# H01R0_Backend.net
KiCad netlist of a schematic drawn in Altium Designer
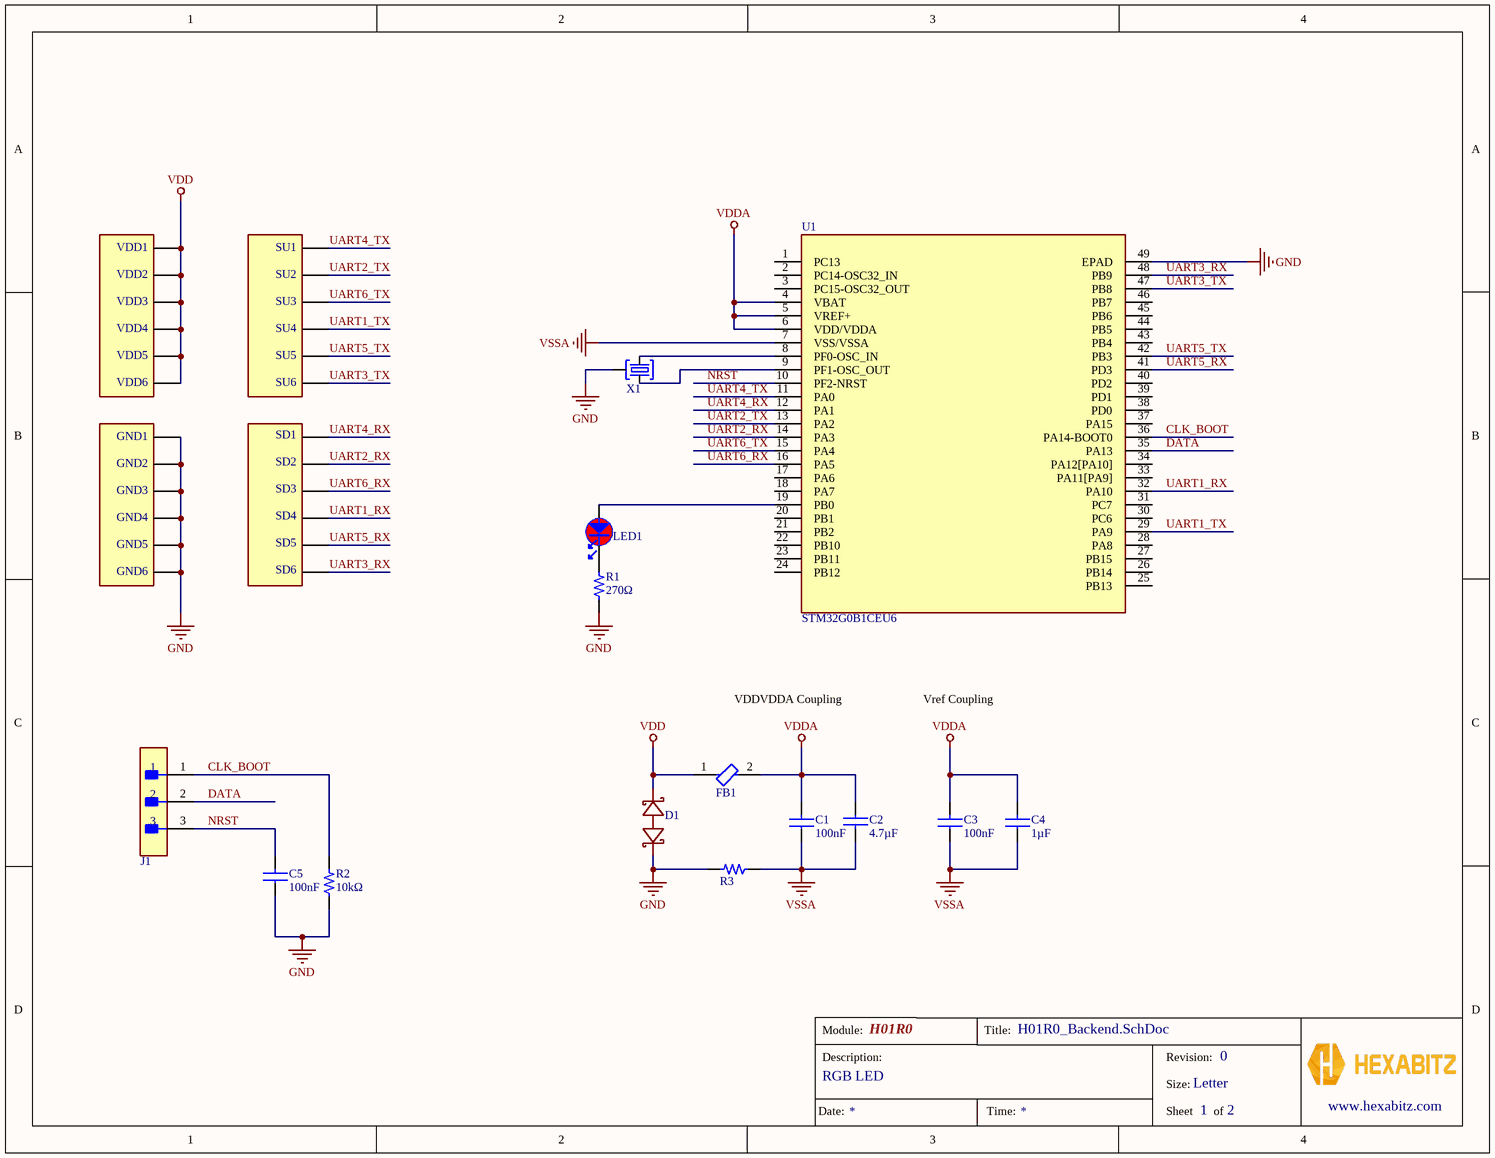
[diagram p0: H01R0_Backend.SchDoc]

(export (version "E")
  (design (tool "Eeschema 10.0.6"))
  (components
    (comp (ref "C1")
      (value "100nF")
      (footprint "C0603")
      (fields
        (field (name "MANUFACTURER") "Samsung Electro-Mechanics")
        (field (name "MANUFACTURER PART NUMBER") "CL10B104KA8NNNC")
        (field (name "TOLERANCE") "10%")
      )
      (libsource (lib "Hexabitz Altium Library") (part "generic Capacitor"))
    )
    (comp (ref "C2")
      (value "4.7µF")
      (footprint "C0805")
      (fields
        (field (name "MANUFACTURER") "Samsung Electro-Mechanics")
        (field (name "MANUFACTURER PART NUMBER") "CL21X475KAQNNNE")
        (field (name "TOLERANCE") "10%")
      )
      (libsource (lib "Hexabitz Altium Library") (part "generic Capacitor"))
    )
    (comp (ref "C3")
      (value "100nF")
      (footprint "C0603")
      (fields
        (field (name "MANUFACTURER") "Samsung Electro-Mechanics")
        (field (name "MANUFACTURER PART NUMBER") "CL10B104KA8NNNC")
        (field (name "TOLERANCE") "10%")
      )
      (libsource (lib "Hexabitz Altium Library") (part "generic Capacitor"))
    )
    (comp (ref "C4")
      (value "1µF")
      (footprint "C0805")
      (description "Ceramic Capacitor, Ceramic, 16V, 10% +Tol, 10% -Tol, X7R, 15% TC, 1uF, Surface Mount, 0805")
      (fields
        (field (name "MANUFACTURER") "Yageo Group")
        (field (name "MANUFACTURER PART NUMBER") "CC0805KKX7R7BB105")
      )
      (libsource (lib "Hexabitz Altium Library") (part "generic Capacitor"))
    )
    (comp (ref "C5")
      (value "100nF")
      (footprint "C0603")
      (fields
        (field (name "MANUFACTURER") "Samsung Electro-Mechanics")
        (field (name "MANUFACTURER PART NUMBER") "CL10B104KA8NNNC")
        (field (name "TOLERANCE") "10%")
      )
      (libsource (lib "Hexabitz Altium Library") (part "generic Capacitor"))
    )
    (comp (ref "D1")
      (value "CDSOD323-T03SC")
      (footprint "SOD2513X114N")
      (description "A 3V, 350W, bi-directional, standard capacitance, SOD323 pkg TVS Diode ¦ Bourns CDSOD323-T03SC")
      (fields (field (name "MANUFACTURER") "Bourns"))
      (libsource (lib "Hexabitz Altium Library") (part "CDSOD323-T03SC"))
    )
    (comp (ref "FB1")
      (value "MMZ1608Y300B")
      (footprint "FP-MMZ1608-0_8-MFG")
      (description "Ferrite Beads 0603 30ohms 1500mA Signal Line AEC-Q200")
      (fields
        (field (name "MANUFACTURER") "TDK")
        (field (name "MANUFACTURER PART NUMBER") "MMZ1608Y300BTD25")
      )
      (libsource (lib "Hexabitz Altium Library") (part "MMZ1608Y300B"))
    )
    (comp (ref "GND1")
      (value "HEXABIT_UART_PORT")
      (footprint "HEXABIT_POWER_PORT_D")
      (libsource (lib "hexabitz_connectors.Library") (part "HEXABIT_POWER_PORT_D"))
    )
    (comp (ref "GND2")
      (value "HEXABIT_UART_PORT")
      (footprint "HEXABIT_POWER_PORT_D")
      (libsource (lib "hexabitz_connectors.Library") (part "HEXABIT_POWER_PORT_D"))
    )
    (comp (ref "GND3")
      (value "HEXABIT_UART_PORT")
      (footprint "HEXABIT_POWER_PORT_D")
      (libsource (lib "hexabitz_connectors.Library") (part "HEXABIT_POWER_PORT_D"))
    )
    (comp (ref "GND4")
      (value "HEXABIT_UART_PORT")
      (footprint "HEXABIT_POWER_PORT_D")
      (libsource (lib "hexabitz_connectors.Library") (part "HEXABIT_POWER_PORT_D"))
    )
    (comp (ref "GND5")
      (value "HEXABIT_UART_PORT")
      (footprint "HEXABIT_POWER_PORT_D")
      (libsource (lib "hexabitz_connectors.Library") (part "HEXABIT_POWER_PORT_D"))
    )
    (comp (ref "GND6")
      (value "HEXABIT_UART_PORT")
      (footprint "HEXABIT_POWER_PORT_D")
      (libsource (lib "hexabitz_connectors.Library") (part "HEXABIT_POWER_PORT_D"))
    )
    (comp (ref "J1")
      (value "TSW-103-14-G-S")
      (footprint "FP-TSW-103-14-G-S-MFG")
      (description "CONN HEADER VERT 3POS 2.54MM")
      (libsource (lib "Altium Content Vault") (part "cd3439d6ef35ae5d9b27ec4fdd3e828"))
    )
    (comp (ref "LED1")
      (value "VLMS1300-GS08")
      (footprint "FP-6_541-5092_01-4-MFG")
      (description "LED Uni-Color Super Red 639nm 2-Pin Chip 0603(1608Metric) T/R")
      (fields (field (name "MANUFACTURER") "Vishay Semiconductors"))
      (libsource (lib "Hexabitz Altium Library") (part "VLMS1300-GS08"))
    )
    (comp (ref "R1")
      (value "270Ω")
      (footprint "R0603")
      (description "Res Thick Film 0603 270 Ohm 5% 0.1W(1/10W) ±200ppm/C Pad SMD Automotive T/R")
      (fields
        (field (name "MANUFACTURER") "Panasonic")
        (field (name "MANUFACTURER PART NUMBER") "ERJ-3GEYJ271V")
      )
      (libsource (lib "Hexabitz Altium Library") (part "generic Resistor"))
    )
    (comp (ref "R2")
      (value "10kΩ")
      (footprint "R0603")
      (description "100mW Thick Film Resistors ±100ppm/℃ ±1% 10kΩ 0603 Chip Resistor - Surface Mount ROHS")
      (fields
        (field (name "MANUFACTURER") "Yageo Group")
        (field (name "MANUFACTURER PART NUMBER") "RC0603FR-0710KL")
      )
      (libsource (lib "") (part "generic Resistor_1"))
    )
    (comp (ref "R3")
      (value "Manufacturer Part Number")
      (footprint "R0603")
      (libsource (lib "") (part "generic Resistor_2"))
    )
    (comp (ref "SD1")
      (value "HEXABIT_UART_PORT")
      (footprint "HEXABIT_UART_PORT_D")
      (libsource (lib "hexabitz_connectors.Library") (part "HEXABIT_UART_PORT_D"))
    )
    (comp (ref "SD2")
      (value "HEXABIT_UART_PORT")
      (footprint "HEXABIT_UART_PORT_D")
      (libsource (lib "hexabitz_connectors.Library") (part "HEXABIT_UART_PORT_D"))
    )
    (comp (ref "SD3")
      (value "HEXABIT_UART_PORT")
      (footprint "HEXABIT_UART_PORT_D")
      (libsource (lib "hexabitz_connectors.Library") (part "HEXABIT_UART_PORT_D"))
    )
    (comp (ref "SD4")
      (value "HEXABIT_UART_PORT")
      (footprint "HEXABIT_UART_PORT_D")
      (libsource (lib "hexabitz_connectors.Library") (part "HEXABIT_UART_PORT_D"))
    )
    (comp (ref "SD5")
      (value "HEXABIT_UART_PORT")
      (footprint "HEXABIT_UART_PORT_D")
      (libsource (lib "hexabitz_connectors.Library") (part "HEXABIT_UART_PORT_D"))
    )
    (comp (ref "SD6")
      (value "HEXABIT_UART_PORT")
      (footprint "HEXABIT_UART_PORT_D")
      (libsource (lib "hexabitz_connectors.Library") (part "HEXABIT_UART_PORT_D"))
    )
    (comp (ref "SU1")
      (value "HEXABIT_UART_PORT")
      (footprint "HEXABIT_UART_PORT_U")
      (libsource (lib "hexabitz_connectors.Library") (part "HEXABIT_UART_PORT_U"))
    )
    (comp (ref "SU2")
      (value "HEXABIT_UART_PORT")
      (footprint "HEXABIT_UART_PORT_U")
      (libsource (lib "hexabitz_connectors.Library") (part "HEXABIT_UART_PORT_U"))
    )
    (comp (ref "SU3")
      (value "HEXABIT_UART_PORT")
      (footprint "HEXABIT_UART_PORT_U")
      (libsource (lib "hexabitz_connectors.Library") (part "HEXABIT_UART_PORT_U"))
    )
    (comp (ref "SU4")
      (value "HEXABIT_UART_PORT")
      (footprint "HEXABIT_UART_PORT_U")
      (libsource (lib "hexabitz_connectors.Library") (part "HEXABIT_UART_PORT_U"))
    )
    (comp (ref "SU5")
      (value "HEXABIT_UART_PORT")
      (footprint "HEXABIT_UART_PORT_U")
      (libsource (lib "hexabitz_connectors.Library") (part "HEXABIT_UART_PORT_U"))
    )
    (comp (ref "SU6")
      (value "HEXABIT_UART_PORT")
      (footprint "HEXABIT_UART_PORT_U")
      (libsource (lib "hexabitz_connectors.Library") (part "HEXABIT_UART_PORT_U"))
    )
    (comp (ref "U1")
      (value "STM32G0B1CEU6")
      (footprint "QFN50P700X700X65-49N-D")
      (description "MCU 32-bit ARM Cortex M0+ RISC 512KB Flash 1.8V/2.5V/3.3V 48-Pin UFQFPN EP Tray")
      (fields
        (field (name "MANUFACTURER") "STMicroelectronics")
        (field (name "MANUFACTURER PART NUMBER") "STM32G0B1CEU6")
      )
      (libsource (lib "Hexabitz Altium Library") (part "STM32G0B1CEU6"))
    )
    (comp (ref "VDD1")
      (value "HEXABIT_UART_PORT")
      (footprint "HEXABIT_POWER_PORT_U")
      (libsource (lib "hexabitz_connectors.Library") (part "HEXABIT_POWER_PORT_U"))
    )
    (comp (ref "VDD2")
      (value "HEXABIT_UART_PORT")
      (footprint "HEXABIT_POWER_PORT_U")
      (libsource (lib "hexabitz_connectors.Library") (part "HEXABIT_POWER_PORT_U"))
    )
    (comp (ref "VDD3")
      (value "HEXABIT_UART_PORT")
      (footprint "HEXABIT_POWER_PORT_U")
      (libsource (lib "hexabitz_connectors.Library") (part "HEXABIT_POWER_PORT_U"))
    )
    (comp (ref "VDD4")
      (value "HEXABIT_UART_PORT")
      (footprint "HEXABIT_POWER_PORT_U")
      (libsource (lib "hexabitz_connectors.Library") (part "HEXABIT_POWER_PORT_U"))
    )
    (comp (ref "VDD5")
      (value "HEXABIT_UART_PORT")
      (footprint "HEXABIT_POWER_PORT_U")
      (libsource (lib "hexabitz_connectors.Library") (part "HEXABIT_POWER_PORT_U"))
    )
    (comp (ref "VDD6")
      (value "HEXABIT_UART_PORT")
      (footprint "HEXABIT_POWER_PORT_U")
      (libsource (lib "hexabitz_connectors.Library") (part "HEXABIT_POWER_PORT_U"))
    )
    (comp (ref "X1")
      (value "CSTCE8M00G52Z-R0")
      (footprint "XTALL_CSTCE8M00G52")
      (description "Ceramic Resonator 8MHz ±0.5% (Tol) ±0.2% (Stability) 10pF 40Ohm 3-Pin CSMD T/R")
      (fields (field (name "MANUFACTURER") "Murata") (field (name "TOLERANCE") "0.5%"))
      (libsource (lib "Hexabitz Altium Library") (part "CSTCE8M00G52Z-R0"))
    )
  )
  (nets
    (net (code "1") (name "/CLK_BOOT") (class "Default")
      (node (ref "J1") (pin "1") (pinfunction "1_1") (pintype "passive"))
      (node (ref "R2") (pin "1") (pinfunction "1_1") (pintype "passive"))
      (node (ref "U1") (pin "36") (pinfunction "PA14-BOOT0_36") (pintype "passive"))
    )
    (net (code "2") (name "/DATA") (class "Default")
      (node (ref "J1") (pin "2") (pinfunction "2_2") (pintype "passive"))
      (node (ref "U1") (pin "35") (pinfunction "PA13_35") (pintype "passive"))
    )
    (net (code "3") (name "/NRST") (class "Default")
      (node (ref "C5") (pin "2") (pinfunction "2_2") (pintype "passive"))
      (node (ref "J1") (pin "3") (pinfunction "3_3") (pintype "passive"))
      (node (ref "U1") (pin "10") (pinfunction "PF2-NRST_10") (pintype "passive"))
    )
    (net (code "4") (name "/UART1_RX") (class "Default")
      (node (ref "SD4") (pin "UART_D") (pinfunction "UART_D_UART_D") (pintype "passive"))
      (node (ref "U1") (pin "32") (pinfunction "PA10_32") (pintype "passive"))
    )
    (net (code "5") (name "/UART1_TX") (class "Default")
      (node (ref "SU4") (pin "UART_U") (pinfunction "UART_U_UART_U") (pintype "passive"))
      (node (ref "U1") (pin "29") (pinfunction "PA9_29") (pintype "passive"))
    )
    (net (code "6") (name "/UART2_RX") (class "Default")
      (node (ref "SD2") (pin "UART_D") (pinfunction "UART_D_UART_D") (pintype "passive"))
      (node (ref "U1") (pin "14") (pinfunction "PA3_14") (pintype "passive"))
    )
    (net (code "7") (name "/UART2_TX") (class "Default")
      (node (ref "SU2") (pin "UART_U") (pinfunction "UART_U_UART_U") (pintype "passive"))
      (node (ref "U1") (pin "13") (pinfunction "PA2_13") (pintype "passive"))
    )
    (net (code "8") (name "/UART3_RX") (class "Default")
      (node (ref "SD6") (pin "UART_D") (pinfunction "UART_D_UART_D") (pintype "passive"))
      (node (ref "U1") (pin "48") (pinfunction "PB9_48") (pintype "passive"))
    )
    (net (code "9") (name "/UART3_TX") (class "Default")
      (node (ref "SU6") (pin "UART_U") (pinfunction "UART_U_UART_U") (pintype "passive"))
      (node (ref "U1") (pin "47") (pinfunction "PB8_47") (pintype "passive"))
    )
    (net (code "10") (name "/UART4_RX") (class "Default")
      (node (ref "SD1") (pin "UART_D") (pinfunction "UART_D_UART_D") (pintype "passive"))
      (node (ref "U1") (pin "12") (pinfunction "PA1_12") (pintype "passive"))
    )
    (net (code "11") (name "/UART4_TX") (class "Default")
      (node (ref "SU1") (pin "UART_U") (pinfunction "UART_U_UART_U") (pintype "passive"))
      (node (ref "U1") (pin "11") (pinfunction "PA0_11") (pintype "passive"))
    )
    (net (code "12") (name "/UART5_RX") (class "Default")
      (node (ref "SD5") (pin "UART_D") (pinfunction "UART_D_UART_D") (pintype "passive"))
      (node (ref "U1") (pin "41") (pinfunction "PD3_41") (pintype "passive"))
    )
    (net (code "13") (name "/UART5_TX") (class "Default")
      (node (ref "SU5") (pin "UART_U") (pinfunction "UART_U_UART_U") (pintype "passive"))
      (node (ref "U1") (pin "42") (pinfunction "PB3_42") (pintype "passive"))
    )
    (net (code "14") (name "/UART6_RX") (class "Default")
      (node (ref "SD3") (pin "UART_D") (pinfunction "UART_D_UART_D") (pintype "passive"))
      (node (ref "U1") (pin "16") (pinfunction "PA5_16") (pintype "passive"))
    )
    (net (code "15") (name "/UART6_TX") (class "Default")
      (node (ref "SU3") (pin "UART_U") (pinfunction "UART_U_UART_U") (pintype "passive"))
      (node (ref "U1") (pin "15") (pinfunction "PA4_15") (pintype "passive"))
    )
    (net (code "16") (name "GND") (class "Default")
      (node (ref "C5") (pin "1") (pinfunction "1_1") (pintype "passive"))
      (node (ref "D1") (pin "1") (pinfunction "A_1") (pintype "passive"))
      (node (ref "GND1") (pin "Pwr_D") (pinfunction "Pwr_D_Pwr_D") (pintype "passive"))
      (node (ref "GND2") (pin "Pwr_D") (pinfunction "Pwr_D_Pwr_D") (pintype "passive"))
      (node (ref "GND3") (pin "Pwr_D") (pinfunction "Pwr_D_Pwr_D") (pintype "passive"))
      (node (ref "GND4") (pin "Pwr_D") (pinfunction "Pwr_D_Pwr_D") (pintype "passive"))
      (node (ref "GND5") (pin "Pwr_D") (pinfunction "Pwr_D_Pwr_D") (pintype "passive"))
      (node (ref "GND6") (pin "Pwr_D") (pinfunction "Pwr_D_Pwr_D") (pintype "passive"))
      (node (ref "R1") (pin "1") (pinfunction "1_1") (pintype "passive"))
      (node (ref "R2") (pin "2") (pinfunction "2_2") (pintype "passive"))
      (node (ref "R3") (pin "1") (pinfunction "1_1") (pintype "passive"))
      (node (ref "U1") (pin "49") (pinfunction "EPAD_49") (pintype "passive"))
      (node (ref "X1") (pin "P$2") (pinfunction "2_P$2") (pintype "passive"))
    )
    (net (code "17") (name "Net-(LED1-Pad1)") (class "Default")
      (node (ref "LED1") (pin "1") (pintype "passive"))
      (node (ref "R1") (pin "2") (pinfunction "2_2") (pintype "passive"))
    )
    (net (code "18") (name "Net-(U1-PB0)") (class "Default")
      (node (ref "LED1") (pin "2") (pintype "passive"))
      (node (ref "U1") (pin "19") (pinfunction "PB0_19") (pintype "passive"))
    )
    (net (code "19") (name "Net-(U1-PF0-OSC_IN)") (class "Default")
      (node (ref "U1") (pin "8") (pinfunction "PF0-OSC_IN_8") (pintype "passive"))
      (node (ref "X1") (pin "P$3") (pinfunction "3_P$3") (pintype "passive"))
    )
    (net (code "20") (name "Net-(U1-PF1-OSC_OUT)") (class "Default")
      (node (ref "U1") (pin "9") (pinfunction "PF1-OSC_OUT_9") (pintype "passive"))
      (node (ref "X1") (pin "P$1") (pinfunction "1_P$1") (pintype "passive"))
    )
    (net (code "21") (name "VDD") (class "Default")
      (node (ref "D1") (pin "2") (pinfunction "C_2") (pintype "passive"))
      (node (ref "FB1") (pin "1") (pinfunction "1_1") (pintype "passive"))
      (node (ref "VDD1") (pin "Pwr_U") (pinfunction "Pwr_U_Pwr_U") (pintype "passive"))
      (node (ref "VDD2") (pin "Pwr_U") (pinfunction "Pwr_U_Pwr_U") (pintype "passive"))
      (node (ref "VDD3") (pin "Pwr_U") (pinfunction "Pwr_U_Pwr_U") (pintype "passive"))
      (node (ref "VDD4") (pin "Pwr_U") (pinfunction "Pwr_U_Pwr_U") (pintype "passive"))
      (node (ref "VDD5") (pin "Pwr_U") (pinfunction "Pwr_U_Pwr_U") (pintype "passive"))
      (node (ref "VDD6") (pin "Pwr_U") (pinfunction "Pwr_U_Pwr_U") (pintype "passive"))
    )
    (net (code "22") (name "VDDA") (class "Default")
      (node (ref "C1") (pin "2") (pinfunction "2_2") (pintype "passive"))
      (node (ref "C2") (pin "1") (pinfunction "1_1") (pintype "passive"))
      (node (ref "C3") (pin "2") (pinfunction "2_2") (pintype "passive"))
      (node (ref "C4") (pin "2") (pinfunction "2_2") (pintype "passive"))
      (node (ref "FB1") (pin "2") (pinfunction "2_2") (pintype "passive"))
      (node (ref "U1") (pin "4") (pinfunction "VBAT_4") (pintype "passive"))
      (node (ref "U1") (pin "5") (pinfunction "VREF+_5") (pintype "passive"))
      (node (ref "U1") (pin "6") (pinfunction "VDD/VDDA_6") (pintype "passive"))
    )
    (net (code "23") (name "VSSA") (class "Default")
      (node (ref "C1") (pin "1") (pinfunction "1_1") (pintype "passive"))
      (node (ref "C2") (pin "2") (pinfunction "2_2") (pintype "passive"))
      (node (ref "C3") (pin "1") (pinfunction "1_1") (pintype "passive"))
      (node (ref "C4") (pin "1") (pinfunction "1_1") (pintype "passive"))
      (node (ref "R3") (pin "2") (pinfunction "2_2") (pintype "passive"))
      (node (ref "U1") (pin "7") (pinfunction "VSS/VSSA_7") (pintype "passive"))
    )
    (net (code "24") (name "unconnected-(U1-PA6-Pad17)") (class "Default")
      (node (ref "U1") (pin "17") (pinfunction "PA6_17") (pintype "passive"))
    )
    (net (code "25") (name "unconnected-(U1-PA7-Pad18)") (class "Default")
      (node (ref "U1") (pin "18") (pinfunction "PA7_18") (pintype "passive"))
    )
    (net (code "26") (name "unconnected-(U1-PA8-Pad28)") (class "Default")
      (node (ref "U1") (pin "28") (pinfunction "PA8_28") (pintype "passive"))
    )
    (net (code "27") (name "unconnected-(U1-PA11[PA9]-Pad33)") (class "Default")
      (node (ref "U1") (pin "33") (pinfunction "PA11[PA9]_33") (pintype "passive"))
    )
    (net (code "28") (name "unconnected-(U1-PA12[PA10]-Pad34)") (class "Default")
      (node (ref "U1") (pin "34") (pinfunction "PA12[PA10]_34") (pintype "passive"))
    )
    (net (code "29") (name "unconnected-(U1-PA15-Pad37)") (class "Default")
      (node (ref "U1") (pin "37") (pinfunction "PA15_37") (pintype "passive"))
    )
    (net (code "30") (name "unconnected-(U1-PB1-Pad20)") (class "Default")
      (node (ref "U1") (pin "20") (pinfunction "PB1_20") (pintype "passive"))
    )
    (net (code "31") (name "unconnected-(U1-PB2-Pad21)") (class "Default")
      (node (ref "U1") (pin "21") (pinfunction "PB2_21") (pintype "passive"))
    )
    (net (code "32") (name "unconnected-(U1-PB4-Pad43)") (class "Default")
      (node (ref "U1") (pin "43") (pinfunction "PB4_43") (pintype "passive"))
    )
    (net (code "33") (name "unconnected-(U1-PB5-Pad44)") (class "Default")
      (node (ref "U1") (pin "44") (pinfunction "PB5_44") (pintype "passive"))
    )
    (net (code "34") (name "unconnected-(U1-PB6-Pad45)") (class "Default")
      (node (ref "U1") (pin "45") (pinfunction "PB6_45") (pintype "passive"))
    )
    (net (code "35") (name "unconnected-(U1-PB7-Pad46)") (class "Default")
      (node (ref "U1") (pin "46") (pinfunction "PB7_46") (pintype "passive"))
    )
    (net (code "36") (name "unconnected-(U1-PB10-Pad22)") (class "Default")
      (node (ref "U1") (pin "22") (pinfunction "PB10_22") (pintype "passive"))
    )
    (net (code "37") (name "unconnected-(U1-PB11-Pad23)") (class "Default")
      (node (ref "U1") (pin "23") (pinfunction "PB11_23") (pintype "passive"))
    )
    (net (code "38") (name "unconnected-(U1-PB12-Pad24)") (class "Default")
      (node (ref "U1") (pin "24") (pinfunction "PB12_24") (pintype "passive"))
    )
    (net (code "39") (name "unconnected-(U1-PB13-Pad25)") (class "Default")
      (node (ref "U1") (pin "25") (pinfunction "PB13_25") (pintype "passive"))
    )
    (net (code "40") (name "unconnected-(U1-PB14-Pad26)") (class "Default")
      (node (ref "U1") (pin "26") (pinfunction "PB14_26") (pintype "passive"))
    )
    (net (code "41") (name "unconnected-(U1-PB15-Pad27)") (class "Default")
      (node (ref "U1") (pin "27") (pinfunction "PB15_27") (pintype "passive"))
    )
    (net (code "42") (name "unconnected-(U1-PC6-Pad30)") (class "Default")
      (node (ref "U1") (pin "30") (pinfunction "PC6_30") (pintype "passive"))
    )
    (net (code "43") (name "unconnected-(U1-PC7-Pad31)") (class "Default")
      (node (ref "U1") (pin "31") (pinfunction "PC7_31") (pintype "passive"))
    )
    (net (code "44") (name "unconnected-(U1-PC13-Pad1)") (class "Default")
      (node (ref "U1") (pin "1") (pinfunction "PC13_1") (pintype "passive"))
    )
    (net (code "45") (name "unconnected-(U1-PC14-OSC32_IN-Pad2)") (class "Default")
      (node (ref "U1") (pin "2") (pinfunction "PC14-OSC32_IN_2") (pintype "passive"))
    )
    (net (code "46") (name "unconnected-(U1-PC15-OSC32_OUT-Pad3)") (class "Default")
      (node (ref "U1") (pin "3") (pinfunction "PC15-OSC32_OUT_3") (pintype "passive"))
    )
    (net (code "47") (name "unconnected-(U1-PD0-Pad38)") (class "Default")
      (node (ref "U1") (pin "38") (pinfunction "PD0_38") (pintype "passive"))
    )
    (net (code "48") (name "unconnected-(U1-PD1-Pad39)") (class "Default")
      (node (ref "U1") (pin "39") (pinfunction "PD1_39") (pintype "passive"))
    )
    (net (code "49") (name "unconnected-(U1-PD2-Pad40)") (class "Default")
      (node (ref "U1") (pin "40") (pinfunction "PD2_40") (pintype "passive"))
    )
  )
)
